# q2.net
KiCad netlist of a schematic drawn in EAGLE
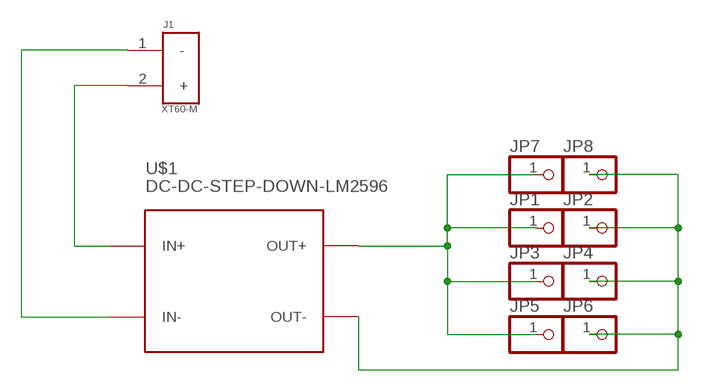
[diagram p0: schematic, sheet 1]

(export (version "E")
  (design (tool "Eeschema 10.0.6"))
  (components
    (comp (ref "J1")
      (value "XT60-M")
      (footprint "eagle-import:AMASS_XT60-M")
      (fields (field (name "MF") "AMASS"))
      (libsource (lib "eagle-import") (part "XT60-M"))
    )
    (comp (ref "JP1")
      (value "PINHD-1X1")
      (footprint "eagle-import:1X01")
      (libsource (lib "eagle-import") (part "PINHD-1X1"))
    )
    (comp (ref "JP2")
      (value "PINHD-1X1")
      (footprint "eagle-import:1X01")
      (libsource (lib "eagle-import") (part "PINHD-1X1"))
    )
    (comp (ref "JP3")
      (value "PINHD-1X1")
      (footprint "eagle-import:1X01")
      (libsource (lib "eagle-import") (part "PINHD-1X1"))
    )
    (comp (ref "JP4")
      (value "PINHD-1X1")
      (footprint "eagle-import:1X01")
      (libsource (lib "eagle-import") (part "PINHD-1X1"))
    )
    (comp (ref "JP5")
      (value "PINHD-1X1")
      (footprint "eagle-import:1X01")
      (libsource (lib "eagle-import") (part "PINHD-1X1"))
    )
    (comp (ref "JP6")
      (value "PINHD-1X1")
      (footprint "eagle-import:1X01")
      (libsource (lib "eagle-import") (part "PINHD-1X1"))
    )
    (comp (ref "JP7")
      (value "PINHD-1X1")
      (footprint "eagle-import:1X01")
      (libsource (lib "eagle-import") (part "PINHD-1X1"))
    )
    (comp (ref "JP8")
      (value "PINHD-1X1")
      (footprint "eagle-import:1X01")
      (libsource (lib "eagle-import") (part "PINHD-1X1"))
    )
    (comp (ref "U$1")
      (value "DC-DC-STEP-DOWN-LM2596")
      (footprint "eagle-import:DC-DC-STEP-DOWN-LM2596")
      (libsource (lib "eagle-import") (part "DC-DC-STEP-DOWN-LM2596"))
    )
  )
  (nets
    (net (code "1") (name "Net-(J1-+)") (class "Default")
      (node (ref "J1") (pin "2") (pinfunction "+_2") (pintype "passive"))
      (node (ref "U$1") (pin "IN+") (pinfunction "IN+_IN+") (pintype "bidirectional"))
    )
    (net (code "2") (name "Net-(J1--)") (class "Default")
      (node (ref "J1") (pin "1") (pinfunction "-_1") (pintype "passive"))
      (node (ref "U$1") (pin "IN-") (pinfunction "IN-_IN-") (pintype "bidirectional"))
    )
    (net (code "3") (name "Net-(JP1-Pad1)") (class "Default")
      (node (ref "JP1") (pin "1") (pinfunction "1_1") (pintype "passive"))
      (node (ref "JP3") (pin "1") (pinfunction "1_1") (pintype "passive"))
      (node (ref "JP5") (pin "1") (pinfunction "1_1") (pintype "passive"))
      (node (ref "JP7") (pin "1") (pinfunction "1_1") (pintype "passive"))
      (node (ref "U$1") (pin "OUT+") (pinfunction "OUT+_OUT+") (pintype "bidirectional"))
    )
    (net (code "4") (name "Net-(JP2-Pad1)") (class "Default")
      (node (ref "JP2") (pin "1") (pinfunction "1_1") (pintype "passive"))
      (node (ref "JP4") (pin "1") (pinfunction "1_1") (pintype "passive"))
      (node (ref "JP6") (pin "1") (pinfunction "1_1") (pintype "passive"))
      (node (ref "JP8") (pin "1") (pinfunction "1_1") (pintype "passive"))
      (node (ref "U$1") (pin "OUT-") (pinfunction "OUT-_OUT-") (pintype "bidirectional"))
    )
  )
)
